# IFS2DSM.net
KiCad netlist of a schematic drawn in EAGLE
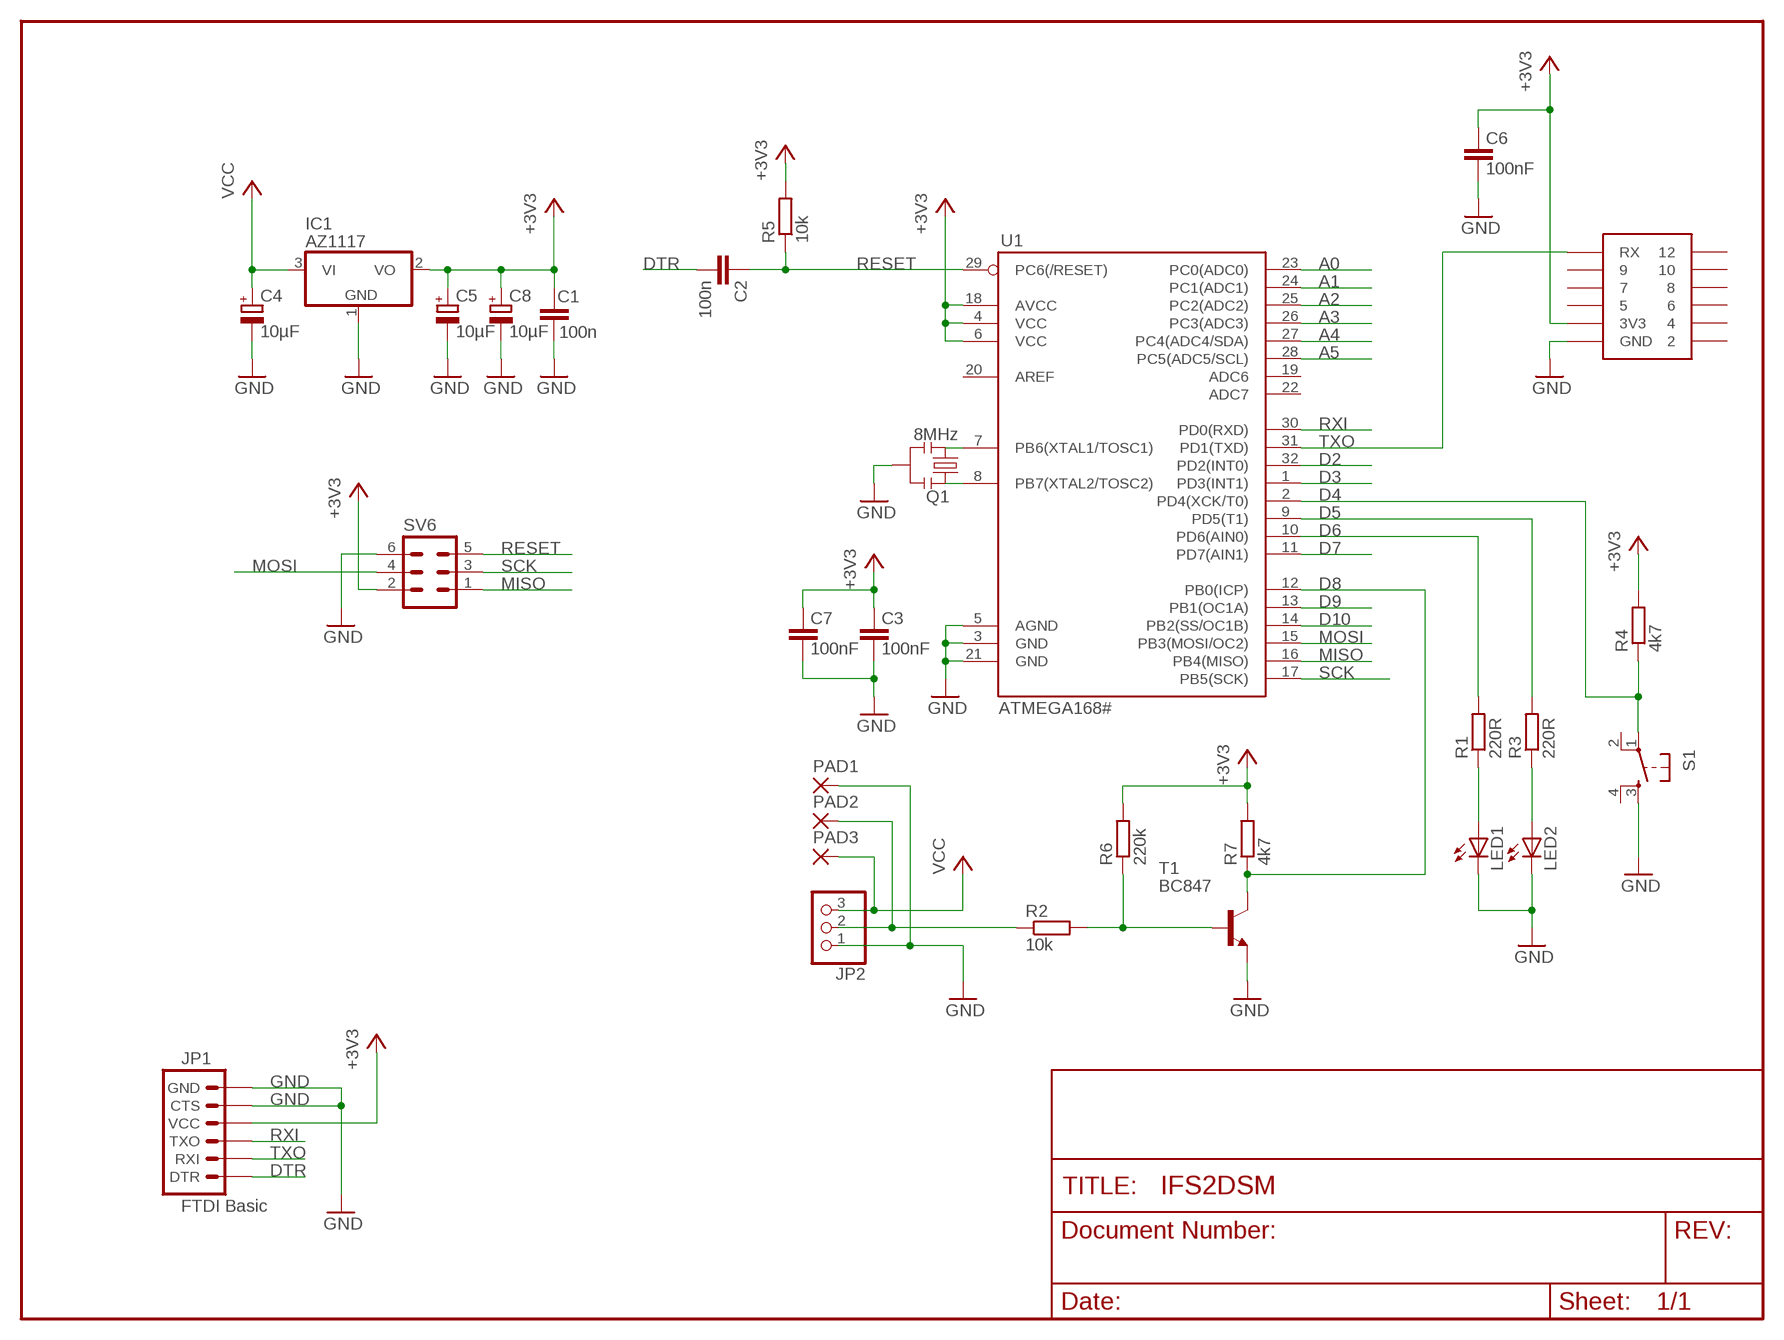
[diagram p0: schematic, sheet 1]

(export (version "E")
  (design (tool "Eeschema 10.0.6"))
  (components
    (comp (ref "C1")
      (value "100n")
      (footprint "eagle-import:C0805")
      (libsource (lib "eagle-import") (part "C-EUC0805"))
    )
    (comp (ref "C2")
      (value "100n")
      (footprint "eagle-import:C0805")
      (libsource (lib "eagle-import") (part "C-EUC0805"))
    )
    (comp (ref "C3")
      (value "100nF")
      (footprint "eagle-import:C0805")
      (libsource (lib "eagle-import") (part "C-EUC0805"))
    )
    (comp (ref "C4")
      (value "10µF")
      (footprint "eagle-import:CT6032")
      (libsource (lib "eagle-import") (part "CPOL-EUCT6032"))
    )
    (comp (ref "C5")
      (value "10µF")
      (footprint "eagle-import:CT6032")
      (libsource (lib "eagle-import") (part "CPOL-EUCT6032"))
    )
    (comp (ref "C6")
      (value "100nF")
      (footprint "eagle-import:C0805")
      (libsource (lib "eagle-import") (part "C-EUC0805"))
    )
    (comp (ref "C7")
      (value "100nF")
      (footprint "eagle-import:C0805")
      (libsource (lib "eagle-import") (part "C-EUC0805"))
    )
    (comp (ref "C8")
      (value "10µF")
      (footprint "eagle-import:CT6032")
      (libsource (lib "eagle-import") (part "CPOL-EUCT6032"))
    )
    (comp (ref "IC1")
      (value "AZ1117")
      (footprint "eagle-import:SOT223")
      (libsource (lib "eagle-import") (part "AZ1117"))
    )
    (comp (ref "IC3")
      (value "X1TX0")
      (footprint "eagle-import:X1TX0")
      (libsource (lib "eagle-import") (part "X1TX0"))
    )
    (comp (ref "JP1")
      (value "FTDI Basic")
      (footprint "eagle-import:1X06")
      (libsource (lib "eagle-import") (part "ARDUINO_SERIAL_PROGRAMPTH"))
    )
    (comp (ref "JP2")
      (value "PINHD-1X3_2.00")
      (footprint "eagle-import:1X03M")
      (libsource (lib "eagle-import") (part "PINHD-1X3_2.00"))
    )
    (comp (ref "LED1")
      (value "LEDSML0805")
      (footprint "eagle-import:SML0805")
      (libsource (lib "eagle-import") (part "LEDSML0805"))
    )
    (comp (ref "LED2")
      (value "LEDSML0805")
      (footprint "eagle-import:SML0805")
      (libsource (lib "eagle-import") (part "LEDSML0805"))
    )
    (comp (ref "PAD1")
      (value "SMD2")
      (footprint "eagle-import:SMD1,27-2,54")
      (libsource (lib "eagle-import") (part "SMD2"))
    )
    (comp (ref "PAD2")
      (value "SMD2")
      (footprint "eagle-import:SMD1,27-2,54")
      (libsource (lib "eagle-import") (part "SMD2"))
    )
    (comp (ref "PAD3")
      (value "SMD2")
      (footprint "eagle-import:SMD1,27-2,54")
      (libsource (lib "eagle-import") (part "SMD2"))
    )
    (comp (ref "Q1")
      (value "8MHz")
      (footprint "eagle-import:RESONATOR-SMD")
      (libsource (lib "eagle-import") (part "RESONATORSMD"))
    )
    (comp (ref "R1")
      (value "220R")
      (footprint "eagle-import:R0805")
      (libsource (lib "eagle-import") (part "R-EU_R0805"))
    )
    (comp (ref "R2")
      (value "10k")
      (footprint "eagle-import:R0805")
      (libsource (lib "eagle-import") (part "R-EU_R0805"))
    )
    (comp (ref "R3")
      (value "220R")
      (footprint "eagle-import:R0805")
      (libsource (lib "eagle-import") (part "R-EU_R0805"))
    )
    (comp (ref "R4")
      (value "4k7")
      (footprint "eagle-import:R0805")
      (libsource (lib "eagle-import") (part "R-EU_R0805"))
    )
    (comp (ref "R5")
      (value "10k")
      (footprint "eagle-import:R0805")
      (libsource (lib "eagle-import") (part "R-EU_R0805"))
    )
    (comp (ref "R6")
      (value "220k")
      (footprint "eagle-import:R0805")
      (libsource (lib "eagle-import") (part "R-EU_R0805"))
    )
    (comp (ref "R7")
      (value "4k7")
      (footprint "eagle-import:R0805")
      (libsource (lib "eagle-import") (part "R-EU_R0805"))
    )
    (comp (ref "S1")
      (value "10-XXTASTERSMD")
      (footprint "eagle-import:SMD")
      (libsource (lib "eagle-import") (part "10-XXTASTERSMD"))
    )
    (comp (ref "SV6")
      (value "MA03-2")
      (footprint "eagle-import:MA03-2")
      (libsource (lib "eagle-import") (part "MA03-2"))
    )
    (comp (ref "T1")
      (value "BC847")
      (footprint "eagle-import:SOT23")
      (libsource (lib "eagle-import") (part "BC847"))
    )
    (comp (ref "U1")
      (value "ATMEGA168#")
      (footprint "eagle-import:TQFP32-08")
      (libsource (lib "eagle-import") (part "ATMEGA168"))
    )
  )
  (nets
    (net (code "1") (name "+3V3") (class "Default")
      (node (ref "C1") (pin "2") (pinfunction "2_2") (pintype "passive"))
      (node (ref "C3") (pin "2") (pinfunction "2_2") (pintype "passive"))
      (node (ref "C5") (pin "+") (pinfunction "+_+") (pintype "passive"))
      (node (ref "C6") (pin "2") (pinfunction "2_2") (pintype "passive"))
      (node (ref "C7") (pin "2") (pinfunction "2_2") (pintype "passive"))
      (node (ref "C8") (pin "+") (pinfunction "+_+") (pintype "passive"))
      (node (ref "IC1") (pin "2") (pinfunction "VO_2") (pintype "passive"))
      (node (ref "IC3") (pin "3") (pinfunction "3V3_3") (pintype "bidirectional"))
      (node (ref "JP1") (pin "4") (pinfunction "VCC_4") (pintype "passive"))
      (node (ref "R4") (pin "2") (pinfunction "2_2") (pintype "passive"))
      (node (ref "R5") (pin "2") (pinfunction "2_2") (pintype "passive"))
      (node (ref "R6") (pin "2") (pinfunction "2_2") (pintype "passive"))
      (node (ref "R7") (pin "2") (pinfunction "2_2") (pintype "passive"))
      (node (ref "SV6") (pin "2") (pinfunction "2_2") (pintype "passive"))
      (node (ref "U1") (pin "18") (pinfunction "AVCC_18") (pintype "bidirectional"))
      (node (ref "U1") (pin "4") (pinfunction "VCC_4") (pintype "bidirectional"))
      (node (ref "U1") (pin "6") (pinfunction "VCC_6") (pintype "bidirectional"))
    )
    (net (code "2") (name "/2") (class "Default")
      (node (ref "IC3") (pin "2") (pinfunction "2_2") (pintype "power_in"))
    )
    (net (code "3") (name "/4") (class "Default")
      (node (ref "IC3") (pin "4") (pinfunction "4_4") (pintype "power_in"))
    )
    (net (code "4") (name "/A0") (class "Default")
      (node (ref "U1") (pin "23") (pinfunction "PC0(ADC0)_23") (pintype "bidirectional"))
    )
    (net (code "5") (name "/A1") (class "Default")
      (node (ref "U1") (pin "24") (pinfunction "PC1(ADC1)_24") (pintype "bidirectional"))
    )
    (net (code "6") (name "/A2") (class "Default")
      (node (ref "U1") (pin "25") (pinfunction "PC2(ADC2)_25") (pintype "bidirectional"))
    )
    (net (code "7") (name "/A3") (class "Default")
      (node (ref "U1") (pin "26") (pinfunction "PC3(ADC3)_26") (pintype "bidirectional"))
    )
    (net (code "8") (name "/A4") (class "Default")
      (node (ref "U1") (pin "27") (pinfunction "PC4(ADC4/SDA)_27") (pintype "bidirectional"))
    )
    (net (code "9") (name "/A5") (class "Default")
      (node (ref "U1") (pin "28") (pinfunction "PC5(ADC5/SCL)_28") (pintype "bidirectional"))
    )
    (net (code "10") (name "/D2") (class "Default")
      (node (ref "U1") (pin "32") (pinfunction "PD2(INT0)_32") (pintype "bidirectional"))
    )
    (net (code "11") (name "/D3") (class "Default")
      (node (ref "U1") (pin "1") (pinfunction "PD3(INT1)_1") (pintype "bidirectional"))
    )
    (net (code "12") (name "/D4") (class "Default")
      (node (ref "R4") (pin "1") (pinfunction "1_1") (pintype "passive"))
      (node (ref "S1") (pin "1") (pinfunction "P_1") (pintype "passive"))
      (node (ref "U1") (pin "2") (pinfunction "PD4(XCK/T0)_2") (pintype "bidirectional"))
    )
    (net (code "13") (name "/D5") (class "Default")
      (node (ref "R3") (pin "2") (pinfunction "2_2") (pintype "passive"))
      (node (ref "U1") (pin "9") (pinfunction "PD5(T1)_9") (pintype "bidirectional"))
    )
    (net (code "14") (name "/D6") (class "Default")
      (node (ref "R1") (pin "2") (pinfunction "2_2") (pintype "passive"))
      (node (ref "U1") (pin "10") (pinfunction "PD6(AIN0)_10") (pintype "bidirectional"))
    )
    (net (code "15") (name "/D7") (class "Default")
      (node (ref "U1") (pin "11") (pinfunction "PD7(AIN1)_11") (pintype "bidirectional"))
    )
    (net (code "16") (name "/D8") (class "Default")
      (node (ref "R7") (pin "1") (pinfunction "1_1") (pintype "passive"))
      (node (ref "T1") (pin "3") (pinfunction "C_3") (pintype "passive"))
      (node (ref "U1") (pin "12") (pinfunction "PB0(ICP)_12") (pintype "bidirectional"))
    )
    (net (code "17") (name "/D9") (class "Default")
      (node (ref "U1") (pin "13") (pinfunction "PB1(OC1A)_13") (pintype "bidirectional"))
    )
    (net (code "18") (name "/D10") (class "Default")
      (node (ref "U1") (pin "14") (pinfunction "PB2(SS/OC1B)_14") (pintype "bidirectional"))
    )
    (net (code "19") (name "/DTR") (class "Default")
      (node (ref "C2") (pin "2") (pinfunction "2_2") (pintype "passive"))
      (node (ref "JP1") (pin "1") (pinfunction "DTR_1") (pintype "passive"))
    )
    (net (code "20") (name "/MISO") (class "Default")
      (node (ref "SV6") (pin "1") (pinfunction "1_1") (pintype "passive"))
      (node (ref "U1") (pin "16") (pinfunction "PB4(MISO)_16") (pintype "bidirectional"))
    )
    (net (code "21") (name "/MOSI") (class "Default")
      (node (ref "SV6") (pin "4") (pinfunction "4_4") (pintype "passive"))
      (node (ref "U1") (pin "15") (pinfunction "PB3(MOSI/OC2)_15") (pintype "bidirectional"))
    )
    (net (code "22") (name "/RESET") (class "Default")
      (node (ref "C2") (pin "1") (pinfunction "1_1") (pintype "passive"))
      (node (ref "R5") (pin "1") (pinfunction "1_1") (pintype "passive"))
      (node (ref "SV6") (pin "5") (pinfunction "5_5") (pintype "passive"))
      (node (ref "U1") (pin "29") (pinfunction "PC6(/RESET)_29") (pintype "bidirectional"))
    )
    (net (code "23") (name "/RXI") (class "Default")
      (node (ref "JP1") (pin "3") (pinfunction "TXO_3") (pintype "passive"))
      (node (ref "U1") (pin "30") (pinfunction "PD0(RXD)_30") (pintype "bidirectional"))
    )
    (net (code "24") (name "/SCK") (class "Default")
      (node (ref "SV6") (pin "3") (pinfunction "3_3") (pintype "passive"))
      (node (ref "U1") (pin "17") (pinfunction "PB5(SCK)_17") (pintype "bidirectional"))
    )
    (net (code "25") (name "/TXO") (class "Default")
      (node (ref "IC3") (pin "11") (pinfunction "RX_11") (pintype "bidirectional"))
      (node (ref "JP1") (pin "2") (pinfunction "RXI_2") (pintype "passive"))
      (node (ref "U1") (pin "31") (pinfunction "PD1(TXD)_31") (pintype "bidirectional"))
    )
    (net (code "26") (name "GND") (class "Default")
      (node (ref "C1") (pin "1") (pinfunction "1_1") (pintype "passive"))
      (node (ref "C3") (pin "1") (pinfunction "1_1") (pintype "passive"))
      (node (ref "C4") (pin "-") (pinfunction "-_-") (pintype "passive"))
      (node (ref "C5") (pin "-") (pinfunction "-_-") (pintype "passive"))
      (node (ref "C6") (pin "1") (pinfunction "1_1") (pintype "passive"))
      (node (ref "C7") (pin "1") (pinfunction "1_1") (pintype "passive"))
      (node (ref "C8") (pin "-") (pinfunction "-_-") (pintype "passive"))
      (node (ref "IC1") (pin "1") (pinfunction "GND_1") (pintype "passive"))
      (node (ref "IC3") (pin "1") (pinfunction "GND_1") (pintype "bidirectional"))
      (node (ref "JP1") (pin "5") (pinfunction "CTS_5") (pintype "passive"))
      (node (ref "JP1") (pin "6") (pinfunction "GND_6") (pintype "passive"))
      (node (ref "JP2") (pin "1") (pinfunction "1_1") (pintype "passive"))
      (node (ref "LED1") (pin "C") (pinfunction "C_C") (pintype "passive"))
      (node (ref "LED2") (pin "C") (pinfunction "C_C") (pintype "passive"))
      (node (ref "PAD1") (pin "1") (pinfunction "P_1") (pintype "passive"))
      (node (ref "Q1") (pin "2") (pinfunction "2_2") (pintype "passive"))
      (node (ref "S1") (pin "3") (pinfunction "S_3") (pintype "passive"))
      (node (ref "SV6") (pin "6") (pinfunction "6_6") (pintype "passive"))
      (node (ref "T1") (pin "2") (pinfunction "E_2") (pintype "passive"))
      (node (ref "U1") (pin "21") (pinfunction "GND_21") (pintype "bidirectional"))
      (node (ref "U1") (pin "3") (pinfunction "GND_3") (pintype "bidirectional"))
      (node (ref "U1") (pin "5") (pinfunction "AGND_5") (pintype "bidirectional"))
    )
    (net (code "27") (name "Net-(LED1-PadA)") (class "Default")
      (node (ref "LED1") (pin "A") (pinfunction "A_A") (pintype "passive"))
      (node (ref "R1") (pin "1") (pinfunction "1_1") (pintype "passive"))
    )
    (net (code "28") (name "Net-(LED2-PadA)") (class "Default")
      (node (ref "LED2") (pin "A") (pinfunction "A_A") (pintype "passive"))
      (node (ref "R3") (pin "1") (pinfunction "1_1") (pintype "passive"))
    )
    (net (code "29") (name "Net-(PAD2-P)") (class "Default")
      (node (ref "JP2") (pin "2") (pinfunction "2_2") (pintype "passive"))
      (node (ref "PAD2") (pin "1") (pinfunction "P_1") (pintype "passive"))
      (node (ref "R2") (pin "1") (pinfunction "1_1") (pintype "passive"))
    )
    (net (code "30") (name "Net-(T1-B)") (class "Default")
      (node (ref "R2") (pin "2") (pinfunction "2_2") (pintype "passive"))
      (node (ref "R6") (pin "1") (pinfunction "1_1") (pintype "passive"))
      (node (ref "T1") (pin "1") (pinfunction "B_1") (pintype "passive"))
    )
    (net (code "31") (name "Net-(U1-PB6(XTAL1{slash}TOSC1))") (class "Default")
      (node (ref "Q1") (pin "3") (pinfunction "3_3") (pintype "passive"))
      (node (ref "U1") (pin "7") (pinfunction "PB6(XTAL1/TOSC1)_7") (pintype "bidirectional"))
    )
    (net (code "32") (name "Net-(U1-PB7(XTAL2{slash}TOSC2))") (class "Default")
      (node (ref "Q1") (pin "1") (pinfunction "1_1") (pintype "passive"))
      (node (ref "U1") (pin "8") (pinfunction "PB7(XTAL2/TOSC2)_8") (pintype "bidirectional"))
    )
    (net (code "33") (name "VCC") (class "Default")
      (node (ref "C4") (pin "+") (pinfunction "+_+") (pintype "passive"))
      (node (ref "IC1") (pin "3") (pinfunction "VI_3") (pintype "input"))
      (node (ref "JP2") (pin "3") (pinfunction "3_3") (pintype "passive"))
      (node (ref "PAD3") (pin "1") (pinfunction "P_1") (pintype "passive"))
    )
    (net (code "34") (name "unconnected-(IC3-Pad5)") (class "Default")
      (node (ref "IC3") (pin "5") (pinfunction "5_5") (pintype "bidirectional"))
    )
    (net (code "35") (name "unconnected-(IC3-Pad6)") (class "Default")
      (node (ref "IC3") (pin "6") (pinfunction "6_6") (pintype "bidirectional"))
    )
    (net (code "36") (name "unconnected-(IC3-Pad7)") (class "Default")
      (node (ref "IC3") (pin "7") (pinfunction "7_7") (pintype "bidirectional"))
    )
    (net (code "37") (name "unconnected-(IC3-Pad8)") (class "Default")
      (node (ref "IC3") (pin "8") (pinfunction "8_8") (pintype "bidirectional"))
    )
    (net (code "38") (name "unconnected-(IC3-Pad9)") (class "Default")
      (node (ref "IC3") (pin "9") (pinfunction "9_9") (pintype "bidirectional"))
    )
    (net (code "39") (name "unconnected-(IC3-Pad10)") (class "Default")
      (node (ref "IC3") (pin "10") (pinfunction "10_10") (pintype "bidirectional"))
    )
    (net (code "40") (name "unconnected-(IC3-Pad12)") (class "Default")
      (node (ref "IC3") (pin "12") (pinfunction "12_12") (pintype "input"))
    )
    (net (code "41") (name "unconnected-(S1-P1-Pad2)") (class "Default")
      (node (ref "S1") (pin "2") (pinfunction "P1_2") (pintype "passive"))
    )
    (net (code "42") (name "unconnected-(S1-S1-Pad4)") (class "Default")
      (node (ref "S1") (pin "4") (pinfunction "S1_4") (pintype "passive"))
    )
    (net (code "43") (name "unconnected-(U1-ADC6-Pad19)") (class "Default")
      (node (ref "U1") (pin "19") (pinfunction "ADC6_19") (pintype "bidirectional"))
    )
    (net (code "44") (name "unconnected-(U1-ADC7-Pad22)") (class "Default")
      (node (ref "U1") (pin "22") (pinfunction "ADC7_22") (pintype "bidirectional"))
    )
    (net (code "45") (name "unconnected-(U1-AREF-Pad20)") (class "Default")
      (node (ref "U1") (pin "20") (pinfunction "AREF_20") (pintype "bidirectional"))
    )
  )
)
